# 1_Power.net
KiCad netlist of a schematic drawn in Altium Designer
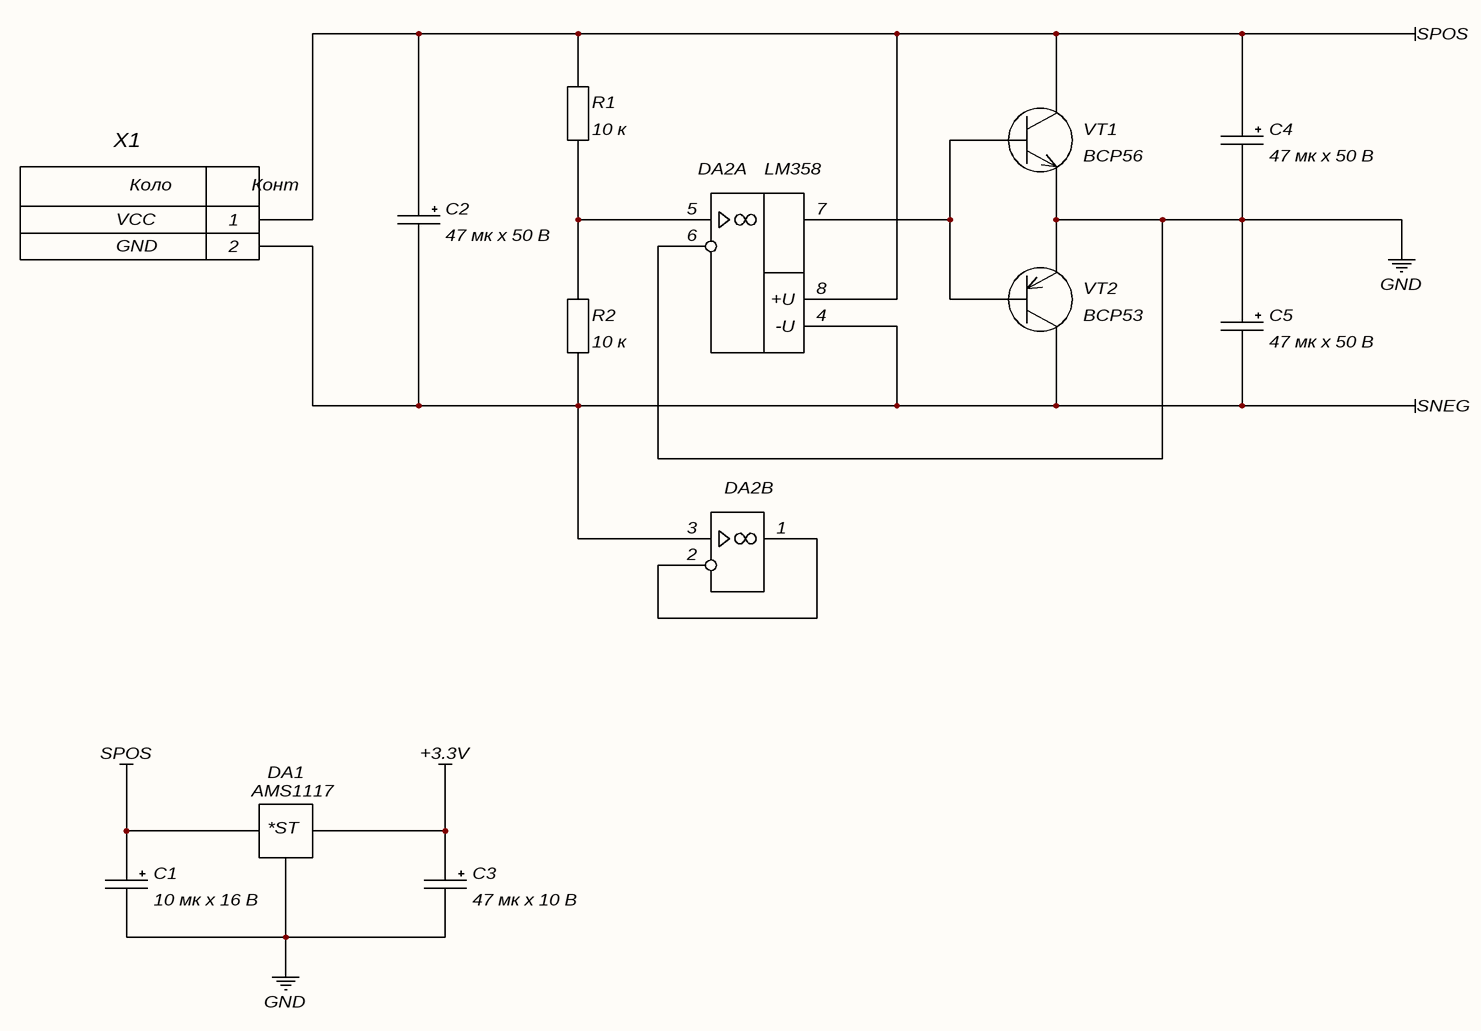
[diagram p0: 1_Power.SchDoc]

(export (version "E")
  (design (tool "Eeschema 10.0.6"))
  (components
    (comp (ref "C1")
      (value "10u 16V")
      (footprint "CAP: TANTAL-A")
      (description "Polarity")
      (fields (field (name "10 16") "10 мк х 16 В"))
      (libsource (lib "DDS_Generator") (part "Capacitor_polar"))
    )
    (comp (ref "C2")
      (value "47u 50V")
      (footprint "CAP: SMD D6.3A6.6H7.7")
      (description "Polarity")
      (fields (field (name "47 50") "47 мк х 50 В"))
      (libsource (lib "DDS_Generator") (part "Capacitor_polar"))
    )
    (comp (ref "C3")
      (value "47u 10V")
      (footprint "CAP: TANTAL-B")
      (description "Polarity")
      (fields (field (name "47 10") "47 мк х 10 В"))
      (libsource (lib "DDS_Generator") (part "Capacitor_polar"))
    )
    (comp (ref "C4")
      (value "47u 50V")
      (footprint "CAP: SMD D6.3A6.6H7.7")
      (description "Polarity")
      (fields (field (name "47 50") "47 мк х 50 В"))
      (libsource (lib "DDS_Generator") (part "Capacitor_polar"))
    )
    (comp (ref "C5")
      (value "47u 50V")
      (footprint "CAP: SMD D6.3A6.6H7.7")
      (description "Polarity")
      (fields (field (name "47 50") "47 мк х 50 В"))
      (libsource (lib "DDS_Generator") (part "Capacitor_polar"))
    )
    (comp (ref "DA1")
      (value "AMS1117")
      (footprint "SOT-223")
      (description "3.3V Voltage")
      (fields (field (name "MODEL") "AMS1117"))
      (libsource (lib "DDS_Generator") (part "AMS1117"))
    )
    (comp (ref "DA2")
      (value "LM358")
      (footprint "8-SOIC")
      (fields (field (name "LM358") "LM358"))
      (libsource (lib "DDS_Generator") (part "Op Amp"))
    )
    (comp (ref "R1")
      (value "10k")
      (footprint "RES: 0805")
      (fields (field (name "10 К") "10 к"))
      (libsource (lib "DDS_Generator") (part "Resistor"))
    )
    (comp (ref "R2")
      (value "10k")
      (footprint "RES: 0805")
      (fields (field (name "10 К") "10 к"))
      (libsource (lib "DDS_Generator") (part "Resistor"))
    )
    (comp (ref "VT1")
      (value "BCP56")
      (footprint "SOT-223")
      (fields (field (name "MODEL") "BCP56"))
      (libsource (lib "DDS_Generator") (part "Transistor NPN"))
    )
    (comp (ref "VT2")
      (value "BCP53")
      (footprint "SOT-223")
      (fields (field (name "MODEL") "BCP53"))
      (libsource (lib "DDS_Generator") (part "Transistor PNP"))
    )
    (comp (ref "X1")
      (value "PJ002")
      (footprint "CON: PJ002")
      (libsource (lib "DDS_Generator") (part "DC Jack"))
    )
  )
  (nets
    (net (code "1") (name "+3.3V") (class "Default")
      (node (ref "C3") (pin "1") (pinfunction "1_1") (pintype "passive"))
      (node (ref "DA1") (pin "2") (pinfunction "Vout_2") (pintype "power_in"))
    )
    (net (code "2") (name "GND") (class "Default")
      (node (ref "C1") (pin "2") (pinfunction "2_2") (pintype "passive"))
      (node (ref "C3") (pin "2") (pinfunction "2_2") (pintype "passive"))
      (node (ref "C4") (pin "2") (pinfunction "2_2") (pintype "passive"))
      (node (ref "C5") (pin "1") (pinfunction "1_1") (pintype "passive"))
      (node (ref "DA1") (pin "1") (pinfunction "GND_1") (pintype "power_in"))
      (node (ref "DA2") (pin "6") (pinfunction "-IN1_6") (pintype "passive"))
      (node (ref "VT1") (pin "3") (pinfunction "e_3") (pintype "passive"))
      (node (ref "VT2") (pin "3") (pinfunction "e_3") (pintype "passive"))
    )
    (net (code "3") (name "Net-(DA2A-+IN1)") (class "Default")
      (node (ref "DA2") (pin "5") (pinfunction "+IN1_5") (pintype "passive"))
      (node (ref "R1") (pin "1") (pinfunction "1_1") (pintype "passive"))
      (node (ref "R2") (pin "2") (pinfunction "2_2") (pintype "passive"))
    )
    (net (code "4") (name "Net-(DA2A-OUT1)") (class "Default")
      (node (ref "DA2") (pin "7") (pinfunction "OUT1_7") (pintype "passive"))
      (node (ref "VT1") (pin "1") (pinfunction "b_1") (pintype "passive"))
      (node (ref "VT2") (pin "1") (pinfunction "b_1") (pintype "passive"))
    )
    (net (code "5") (name "Net-(DA2B--IN2)") (class "Default")
      (node (ref "DA2") (pin "1") (pinfunction "OUT2_1") (pintype "passive"))
      (node (ref "DA2") (pin "2") (pinfunction "-IN2_2") (pintype "passive"))
    )
    (net (code "6") (name "SNEG") (class "Default")
      (node (ref "C2") (pin "2") (pinfunction "2_2") (pintype "passive"))
      (node (ref "C5") (pin "2") (pinfunction "2_2") (pintype "passive"))
      (node (ref "DA2") (pin "3") (pinfunction "+IN2_3") (pintype "passive"))
      (node (ref "DA2") (pin "4") (pinfunction "-U_4") (pintype "passive"))
      (node (ref "R2") (pin "1") (pinfunction "1_1") (pintype "passive"))
      (node (ref "VT2") (pin "2") (pinfunction "k_2") (pintype "passive"))
      (node (ref "X1") (pin "2") (pinfunction "2_2") (pintype "power_in"))
    )
    (net (code "7") (name "SPOS") (class "Default")
      (node (ref "C1") (pin "1") (pinfunction "1_1") (pintype "passive"))
      (node (ref "C2") (pin "1") (pinfunction "1_1") (pintype "passive"))
      (node (ref "C4") (pin "1") (pinfunction "1_1") (pintype "passive"))
      (node (ref "DA1") (pin "3") (pinfunction "Vin_3") (pintype "power_in"))
      (node (ref "DA2") (pin "8") (pinfunction "+U_8") (pintype "passive"))
      (node (ref "R1") (pin "2") (pinfunction "2_2") (pintype "passive"))
      (node (ref "VT1") (pin "2") (pinfunction "k_2") (pintype "passive"))
      (node (ref "X1") (pin "1") (pinfunction "1_1") (pintype "passive"))
    )
  )
)
